# untitled.net
KiCad netlist of a schematic drawn in EAGLE
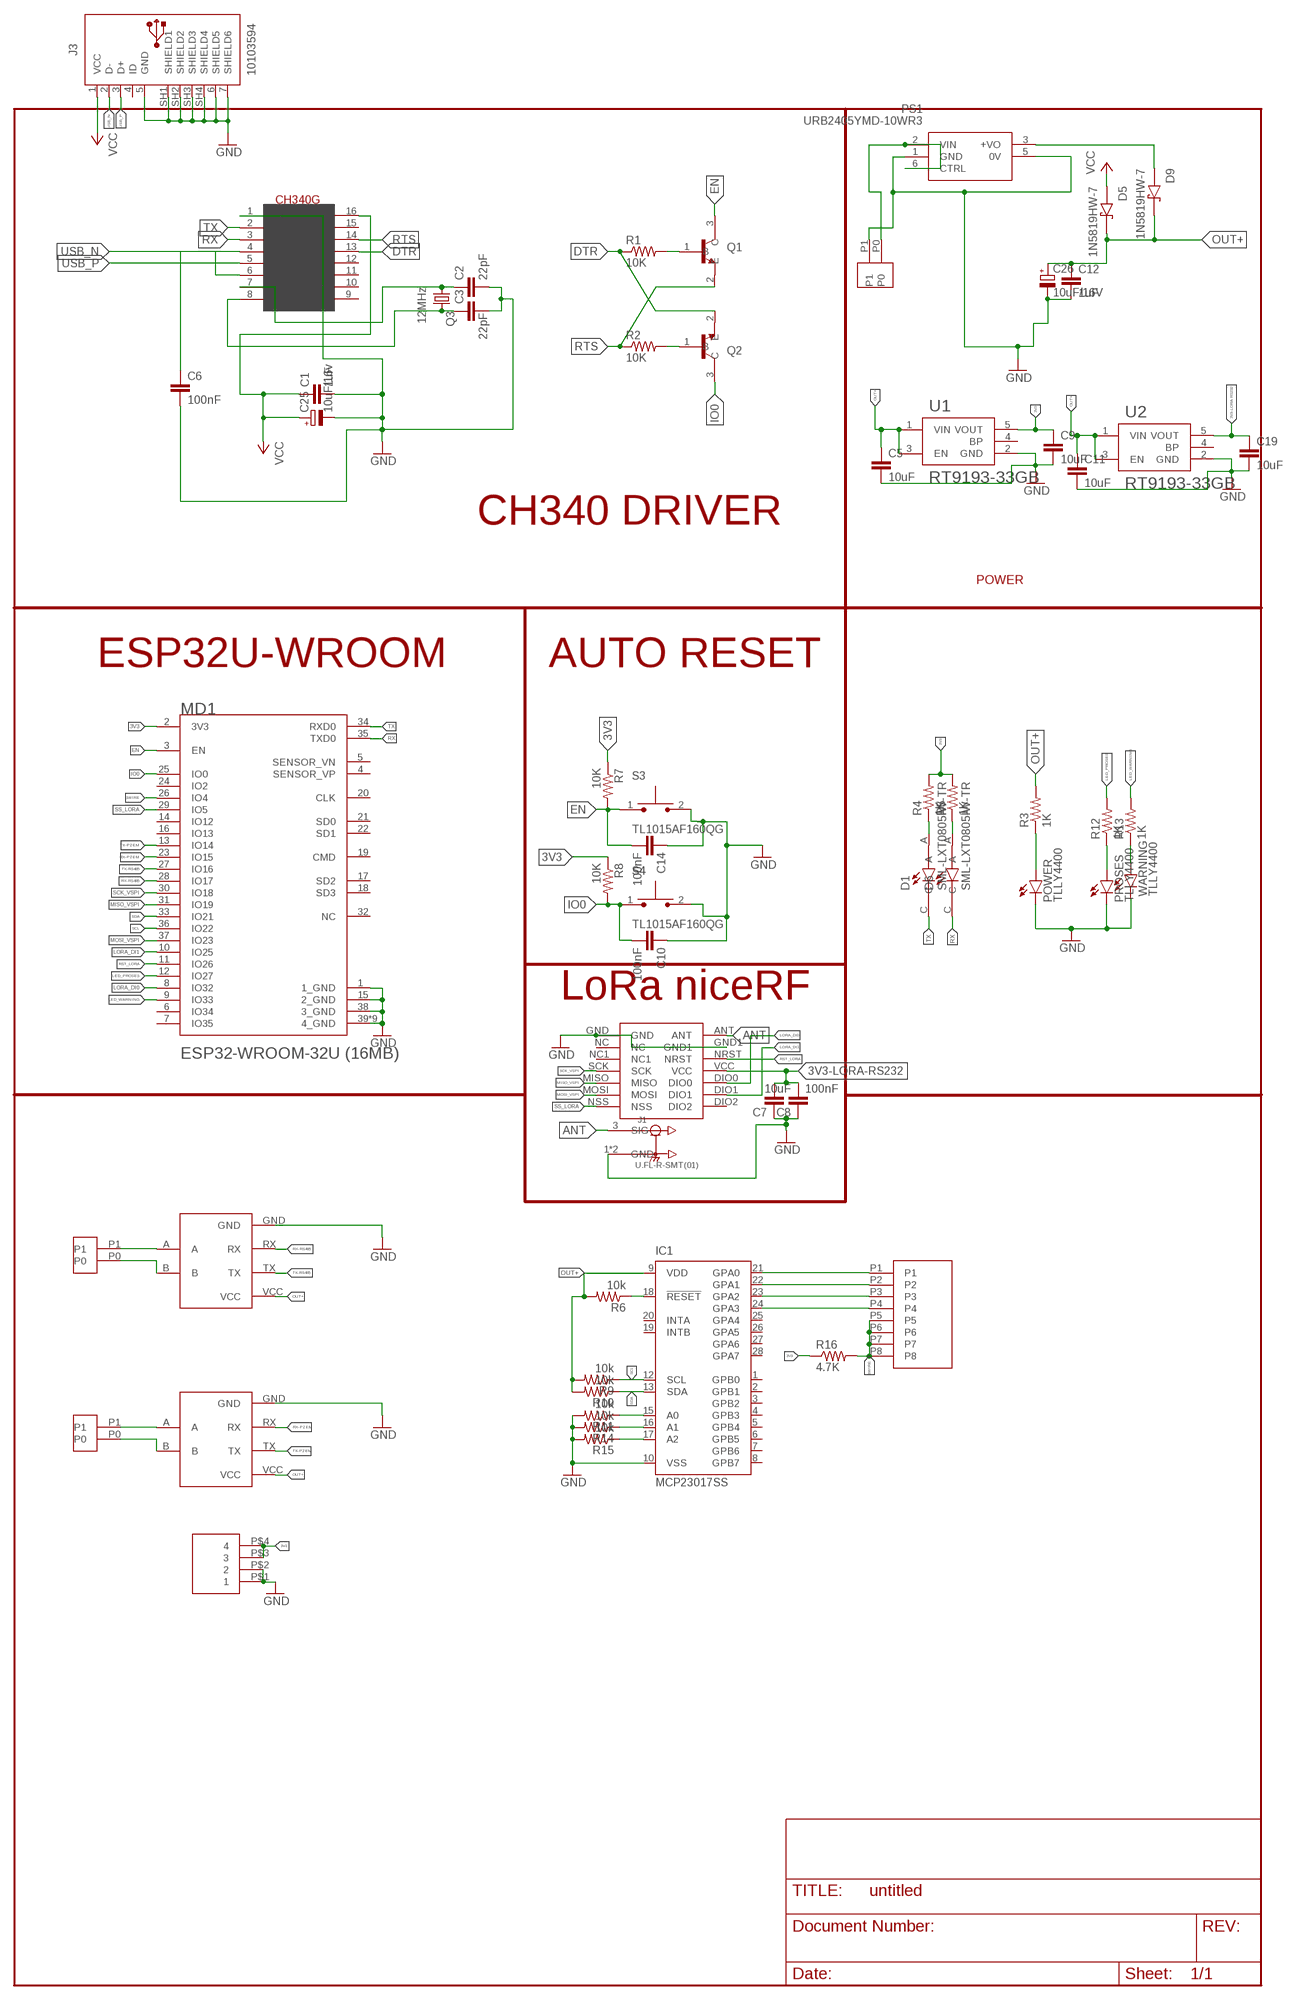
[diagram p0: schematic, sheet 1]

(export (version "E")
  (design (tool "Eeschema 10.0.6"))
  (components
    (comp (ref "C1")
      (value "1uF")
      (footprint "eagle-import:C0805K")
      (libsource (lib "eagle-import") (part "C-EUC0805K"))
    )
    (comp (ref "C2")
      (value "22pF")
      (footprint "eagle-import:C0805K")
      (libsource (lib "eagle-import") (part "C-EUC0805K"))
    )
    (comp (ref "C3")
      (value "22pF")
      (footprint "eagle-import:C0805K")
      (libsource (lib "eagle-import") (part "C-EUC0805K"))
    )
    (comp (ref "C5")
      (value "10uF")
      (footprint "eagle-import:C0805K")
      (libsource (lib "eagle-import") (part "C-EUC0805K"))
    )
    (comp (ref "C6")
      (value "100nF")
      (footprint "eagle-import:C0805K")
      (libsource (lib "eagle-import") (part "C-EUC0805K"))
    )
    (comp (ref "C7")
      (value "10uF")
      (footprint "eagle-import:C0805K")
      (libsource (lib "eagle-import") (part "C-EUC0805K"))
    )
    (comp (ref "C8")
      (value "100nF")
      (footprint "eagle-import:C0805K")
      (libsource (lib "eagle-import") (part "C-EUC0805K"))
    )
    (comp (ref "C9")
      (value "10uF")
      (footprint "eagle-import:C0805K")
      (libsource (lib "eagle-import") (part "C-EUC0805K"))
    )
    (comp (ref "C10")
      (value "100nF")
      (footprint "eagle-import:C0805K")
      (libsource (lib "eagle-import") (part "C-EUC0805K"))
    )
    (comp (ref "C11")
      (value "10uF")
      (footprint "eagle-import:C0805K")
      (libsource (lib "eagle-import") (part "C-EUC0805K"))
    )
    (comp (ref "C12")
      (value "1uF")
      (footprint "eagle-import:C0805K")
      (libsource (lib "eagle-import") (part "C-EUC0805K"))
    )
    (comp (ref "C14")
      (value "100nF")
      (footprint "eagle-import:C0805K")
      (libsource (lib "eagle-import") (part "C-EUC0805K"))
    )
    (comp (ref "C19")
      (value "10uF")
      (footprint "eagle-import:C0805K")
      (libsource (lib "eagle-import") (part "C-EUC0805K"))
    )
    (comp (ref "C25")
      (value "10uF/16v")
      (footprint "eagle-import:153CLV-0505")
      (libsource (lib "eagle-import") (part "CPOL-EU153CLV-0505"))
    )
    (comp (ref "C26")
      (value "10uF/16V")
      (footprint "eagle-import:153CLV-0505")
      (libsource (lib "eagle-import") (part "CPOL-EU153CLV-0505"))
    )
    (comp (ref "CONN2P-3.5PI1")
      (value "CONN2P-3.5PI")
      (footprint "eagle-import:CONN2P-3.5PI")
      (libsource (lib "eagle-import") (part "CONN2P-3.5PI"))
    )
    (comp (ref "CONN2P-3.5PI2")
      (value "CONN2P-3.5PI")
      (footprint "eagle-import:CONN2P-3.5PI")
      (libsource (lib "eagle-import") (part "CONN2P-3.5PI"))
    )
    (comp (ref "CONN2P-3.5PI3")
      (value "CONN2P-3.5PI")
      (footprint "eagle-import:CONN2P-3.5PI")
      (libsource (lib "eagle-import") (part "CONN2P-3.5PI"))
    )
    (comp (ref "CONN3.1")
      (value "CONN3.5")
      (footprint "eagle-import:CONN3.5")
      (libsource (lib "eagle-import") (part "CONN3.5"))
    )
    (comp (ref "D1")
      (value "SML-LXT0805IW-TR")
      (footprint "eagle-import:LEDC2012X120N")
      (fields (field (name "MF") "Lumex Opto/Components"))
      (libsource (lib "eagle-import") (part "SML-LXT0805IW-TR"))
    )
    (comp (ref "D5")
      (value "1N5819HW-7")
      (footprint "eagle-import:SOD3715X145N")
      (fields (field (name "MF") "Diodes Inc."))
      (libsource (lib "eagle-import") (part "1N5819HW-7"))
    )
    (comp (ref "D6")
      (value "SML-LXT0805IW-TR")
      (footprint "eagle-import:LEDC2012X120N")
      (fields (field (name "MF") "Lumex Opto/Components"))
      (libsource (lib "eagle-import") (part "SML-LXT0805IW-TR"))
    )
    (comp (ref "D9")
      (value "1N5819HW-7")
      (footprint "eagle-import:SOD3715X145N")
      (fields (field (name "MF") "Diodes Inc."))
      (libsource (lib "eagle-import") (part "1N5819HW-7"))
    )
    (comp (ref "HEADER-3.81-1")
      (value "HEADER-3.81-4")
      (footprint "eagle-import:HEADER-3.81-4")
      (libsource (lib "eagle-import") (part "HEADER-3.81-4"))
    )
    (comp (ref "IC1")
      (value "MCP23017SS")
      (footprint "eagle-import:SSOP28")
      (fields (field (name "MF") "MICROCHIP") (field (name "MPN") "MCP23017-E/SS"))
      (libsource (lib "eagle-import") (part "MCP23017SS"))
    )
    (comp (ref "J1")
      (value "U.FL-R-SMT(01)")
      (footprint "eagle-import:HRS_U.FL-R-SMT(01)")
      (fields (field (name "MF") "Hirose"))
      (libsource (lib "eagle-import") (part "U.FL-R-SMT(01)"))
    )
    (comp (ref "J3")
      (value "10103594")
      (footprint "eagle-import:10103594")
      (fields (field (name "MANUFACTURER") "Amphenol ICC (FCI)") (field (name "MPN") "10103594-0001LF"))
      (libsource (lib "eagle-import") (part "10103594"))
    )
    (comp (ref "LORA-NICERF-V1")
      (value "LORA-NICERF-V2")
      (footprint "eagle-import:LORA-NICERF-V2")
      (libsource (lib "eagle-import") (part "LORA-NICERF-V2"))
    )
    (comp (ref "MD1")
      (value "ESPRESSIF_SYSTEMS_ESP32-WROOM-32U_16MBESPRESSIF_SYSTEMS_ESP32-WROOM-32U_16MB_0_0")
      (footprint "eagle-import:ESPRESSIF_SYSTEMS_ESP32-WROOM-32U_16MB_0")
      (fields
        (field (name "DIGIKEY_PART_NUMBER") "1904-1028-1-ND")
        (field (name "MF") "Espressif Systems")
        (field (name "MOUSER_PART_NUMBER") "356-ES32WROOM32U16MB")
      )
      (libsource (lib "eagle-import") (part "ESPRESSIF_SYSTEMS_ESP32-WROOM-32U_16MBESPRESSIF_SYSTEMS_ESP32-WROOM-32U_16MB_0_0"))
    )
    (comp (ref "POWER")
      (value "TLLY4400")
      (footprint "eagle-import:LED3MM")
      (fields (field (name "MF") "VISHAY SEMICONDUCTOR"))
      (libsource (lib "eagle-import") (part "TLLY4400"))
    )
    (comp (ref "PROSES")
      (value "TLLY4400")
      (footprint "eagle-import:LED3MM")
      (fields (field (name "MF") "VISHAY SEMICONDUCTOR"))
      (libsource (lib "eagle-import") (part "TLLY4400"))
    )
    (comp (ref "PS1")
      (value "URB2405YMD-10WR3")
      (footprint "eagle-import:URB2405YMD10WR3")
      (libsource (lib "eagle-import") (part "URB2405YMD-10WR3"))
    )
    (comp (ref "Q1")
      (value "MMBT3904")
      (footprint "eagle-import:SOT95P240X120-3N")
      (fields (field (name "MF") "STMicroelectronics"))
      (libsource (lib "eagle-import") (part "MMBT3904"))
    )
    (comp (ref "Q2")
      (value "MMBT3904")
      (footprint "eagle-import:SOT95P240X120-3N")
      (fields (field (name "MF") "STMicroelectronics"))
      (libsource (lib "eagle-import") (part "MMBT3904"))
    )
    (comp (ref "Q3")
      (value "12MHz")
      (footprint "eagle-import:SM49")
      (libsource (lib "eagle-import") (part "CRYSTALSM49"))
    )
    (comp (ref "R1")
      (value "10K")
      (footprint "eagle-import:M0805")
      (libsource (lib "eagle-import") (part "R-US_M0805"))
    )
    (comp (ref "R2")
      (value "10K")
      (footprint "eagle-import:M0805")
      (libsource (lib "eagle-import") (part "R-US_M0805"))
    )
    (comp (ref "R3")
      (value "1K")
      (footprint "eagle-import:M0805")
      (libsource (lib "eagle-import") (part "R-US_M0805"))
    )
    (comp (ref "R4")
      (value "1K")
      (footprint "eagle-import:M0805")
      (libsource (lib "eagle-import") (part "R-US_M0805"))
    )
    (comp (ref "R5")
      (value "1K")
      (footprint "eagle-import:M0805")
      (libsource (lib "eagle-import") (part "R-US_M0805"))
    )
    (comp (ref "R6")
      (value "10k")
      (footprint "eagle-import:M0805")
      (libsource (lib "eagle-import") (part "R-US_M0805"))
    )
    (comp (ref "R7")
      (value "10K")
      (footprint "eagle-import:M0805")
      (libsource (lib "eagle-import") (part "R-US_M0805"))
    )
    (comp (ref "R8")
      (value "10K")
      (footprint "eagle-import:M0805")
      (libsource (lib "eagle-import") (part "R-US_M0805"))
    )
    (comp (ref "R9")
      (value "10k")
      (footprint "eagle-import:M0805")
      (libsource (lib "eagle-import") (part "R-US_M0805"))
    )
    (comp (ref "R10")
      (value "10k")
      (footprint "eagle-import:M0805")
      (libsource (lib "eagle-import") (part "R-US_M0805"))
    )
    (comp (ref "R11")
      (value "10k")
      (footprint "eagle-import:M0805")
      (libsource (lib "eagle-import") (part "R-US_M0805"))
    )
    (comp (ref "R12")
      (value "1K")
      (footprint "eagle-import:M0805")
      (libsource (lib "eagle-import") (part "R-US_M0805"))
    )
    (comp (ref "R13")
      (value "1K")
      (footprint "eagle-import:M0805")
      (libsource (lib "eagle-import") (part "R-US_M0805"))
    )
    (comp (ref "R14")
      (value "10k")
      (footprint "eagle-import:M0805")
      (libsource (lib "eagle-import") (part "R-US_M0805"))
    )
    (comp (ref "R15")
      (value "10k")
      (footprint "eagle-import:M0805")
      (libsource (lib "eagle-import") (part "R-US_M0805"))
    )
    (comp (ref "R16")
      (value "4.7K")
      (footprint "eagle-import:M0805")
      (libsource (lib "eagle-import") (part "R-US_M0805"))
    )
    (comp (ref "S3")
      (value "TL1015AF160QG")
      (footprint "eagle-import:SW_TL1015AF160QG")
      (fields (field (name "MF") "E-Switch"))
      (libsource (lib "eagle-import") (part "TL1015AF160QG"))
    )
    (comp (ref "S4")
      (value "TL1015AF160QG")
      (footprint "eagle-import:SW_TL1015AF160QG")
      (fields (field (name "MF") "E-Switch"))
      (libsource (lib "eagle-import") (part "TL1015AF160QG"))
    )
    (comp (ref "TTL-RS1")
      (value "TTL-RS485")
      (footprint "eagle-import:TTL-RS485")
      (libsource (lib "eagle-import") (part "TTL-RS485"))
    )
    (comp (ref "TTL-RS2")
      (value "TTL-RS485")
      (footprint "eagle-import:TTL-RS485")
      (libsource (lib "eagle-import") (part "TTL-RS485"))
    )
    (comp (ref "U$2")
      (value "CH340G")
      (footprint "eagle-import:SOIC16")
      (libsource (lib "eagle-import") (part "CH340G"))
    )
    (comp (ref "U1")
      (value "RT9193-33GB")
      (footprint "eagle-import:SOT94P279X129-5N")
      (fields (field (name "MF") "Richtek USA Inc."))
      (libsource (lib "eagle-import") (part "RT9193-33GB"))
    )
    (comp (ref "U2")
      (value "RT9193-33GB")
      (footprint "eagle-import:SOT94P279X129-5N")
      (fields (field (name "MF") "Richtek USA Inc."))
      (libsource (lib "eagle-import") (part "RT9193-33GB"))
    )
    (comp (ref "WARNING")
      (value "TLLY4400")
      (footprint "eagle-import:LED3MM")
      (fields (field (name "MF") "VISHAY SEMICONDUCTOR"))
      (libsource (lib "eagle-import") (part "TLLY4400"))
    )
  )
  (nets
    (net (code "1") (name "1WIRE") (class "Default")
      (node (ref "CONN3.1") (pin "P5") (pinfunction "P5_P5") (pintype "bidirectional"))
      (node (ref "CONN3.1") (pin "P6") (pinfunction "P6_P6") (pintype "bidirectional"))
      (node (ref "CONN3.1") (pin "P7") (pinfunction "P7_P7") (pintype "bidirectional"))
      (node (ref "CONN3.1") (pin "P8") (pinfunction "P8_P8") (pintype "bidirectional"))
      (node (ref "MD1") (pin "26") (pinfunction "IO4_26") (pintype "bidirectional"))
      (node (ref "R16") (pin "2") (pinfunction "2_2") (pintype "passive"))
    )
    (net (code "2") (name "3V3") (class "Default")
      (node (ref "C9") (pin "1") (pinfunction "1_1") (pintype "passive"))
      (node (ref "HEADER-3.81-1") (pin "P$3") (pinfunction "3_P$3") (pintype "bidirectional"))
      (node (ref "HEADER-3.81-1") (pin "P$4") (pinfunction "4_P$4") (pintype "bidirectional"))
      (node (ref "MD1") (pin "2") (pinfunction "3V3_2") (pintype "power_in"))
      (node (ref "R16") (pin "1") (pinfunction "1_1") (pintype "passive"))
      (node (ref "R4") (pin "2") (pinfunction "2_2") (pintype "passive"))
      (node (ref "R5") (pin "2") (pinfunction "2_2") (pintype "passive"))
      (node (ref "R7") (pin "1") (pinfunction "1_1") (pintype "passive"))
      (node (ref "R8") (pin "1") (pinfunction "1_1") (pintype "passive"))
      (node (ref "U1") (pin "5") (pinfunction "VOUT_5") (pintype "output"))
    )
    (net (code "3") (name "3V3-LORA-RS232") (class "Default")
      (node (ref "C19") (pin "1") (pinfunction "1_1") (pintype "passive"))
      (node (ref "C7") (pin "2") (pinfunction "2_2") (pintype "passive"))
      (node (ref "C8") (pin "2") (pinfunction "2_2") (pintype "passive"))
      (node (ref "LORA-NICERF-V1") (pin "VCC") (pinfunction "VCC_VCC") (pintype "bidirectional"))
      (node (ref "U2") (pin "5") (pinfunction "VOUT_5") (pintype "output"))
    )
    (net (code "4") (name "ANT") (class "Default")
      (node (ref "J1") (pin "3") (pinfunction "SIG_3") (pintype "passive"))
      (node (ref "LORA-NICERF-V1") (pin "ANT") (pinfunction "ANT_ANT") (pintype "bidirectional"))
    )
    (net (code "5") (name "DTR") (class "Default")
      (node (ref "Q2") (pin "2") (pinfunction "E_2") (pintype "passive"))
      (node (ref "R1") (pin "1") (pinfunction "1_1") (pintype "passive"))
      (node (ref "U$2") (pin "13") (pinfunction "DTR_13") (pintype "bidirectional"))
    )
    (net (code "6") (name "EN") (class "Default")
      (node (ref "C14") (pin "2") (pinfunction "2_2") (pintype "passive"))
      (node (ref "MD1") (pin "3") (pinfunction "EN_3") (pintype "input"))
      (node (ref "Q1") (pin "3") (pinfunction "C_3") (pintype "passive"))
      (node (ref "R7") (pin "2") (pinfunction "2_2") (pintype "passive"))
      (node (ref "S3") (pin "1") (pinfunction "1_1") (pintype "passive"))
    )
    (net (code "7") (name "GND") (class "Default")
      (node (ref "C1") (pin "2") (pinfunction "2_2") (pintype "passive"))
      (node (ref "C10") (pin "1") (pinfunction "1_1") (pintype "passive"))
      (node (ref "C11") (pin "2") (pinfunction "2_2") (pintype "passive"))
      (node (ref "C12") (pin "2") (pinfunction "2_2") (pintype "passive"))
      (node (ref "C14") (pin "1") (pinfunction "1_1") (pintype "passive"))
      (node (ref "C19") (pin "2") (pinfunction "2_2") (pintype "passive"))
      (node (ref "C2") (pin "2") (pinfunction "2_2") (pintype "passive"))
      (node (ref "C25") (pin "-") (pinfunction "-_-") (pintype "passive"))
      (node (ref "C26") (pin "-") (pinfunction "-_-") (pintype "passive"))
      (node (ref "C3") (pin "2") (pinfunction "2_2") (pintype "passive"))
      (node (ref "C5") (pin "2") (pinfunction "2_2") (pintype "passive"))
      (node (ref "C6") (pin "2") (pinfunction "2_2") (pintype "passive"))
      (node (ref "C7") (pin "1") (pinfunction "1_1") (pintype "passive"))
      (node (ref "C8") (pin "1") (pinfunction "1_1") (pintype "passive"))
      (node (ref "C9") (pin "2") (pinfunction "2_2") (pintype "passive"))
      (node (ref "CONN2P-3.5PI1") (pin "P1") (pinfunction "P1_P1") (pintype "bidirectional"))
      (node (ref "HEADER-3.81-1") (pin "P$1") (pinfunction "1_P$1") (pintype "bidirectional"))
      (node (ref "HEADER-3.81-1") (pin "P$2") (pinfunction "2_P$2") (pintype "bidirectional"))
      (node (ref "IC1") (pin "10") (pinfunction "VSS_10") (pintype "power_in"))
      (node (ref "J1") (pin "1") (pinfunction "GND_1") (pintype "passive"))
      (node (ref "J1") (pin "2") (pinfunction "GND_2") (pintype "passive"))
      (node (ref "J3") (pin "5") (pinfunction "GND_5") (pintype "power_in"))
      (node (ref "J3") (pin "6") (pinfunction "SHIELD5_6") (pintype "power_in"))
      (node (ref "J3") (pin "7") (pinfunction "SHIELD6_7") (pintype "power_in"))
      (node (ref "J3") (pin "SH1") (pinfunction "SHIELD1_SH1") (pintype "power_in"))
      (node (ref "J3") (pin "SH2") (pinfunction "SHIELD2_SH2") (pintype "power_in"))
      (node (ref "J3") (pin "SH3") (pinfunction "SHIELD3_SH3") (pintype "power_in"))
      (node (ref "J3") (pin "SH4") (pinfunction "SHIELD4_SH4") (pintype "power_in"))
      (node (ref "LORA-NICERF-V1") (pin "GND") (pinfunction "GND_GND") (pintype "bidirectional"))
      (node (ref "LORA-NICERF-V1") (pin "GND1") (pinfunction "GND1_GND1") (pintype "bidirectional"))
      (node (ref "MD1") (pin "1") (pinfunction "1_GND_1") (pintype "power_in"))
      (node (ref "MD1") (pin "15") (pinfunction "2_GND_15") (pintype "power_in"))
      (node (ref "MD1") (pin "38") (pinfunction "3_GND_38") (pintype "power_in"))
      (node (ref "MD1") (pin "39") (pinfunction "4_GND_39") (pintype "power_in"))
      (node (ref "MD1") (pin "39-2") (pinfunction "4_GND_39-2") (pintype "power_in"))
      (node (ref "MD1") (pin "39-3") (pinfunction "4_GND_39-3") (pintype "power_in"))
      (node (ref "MD1") (pin "39-4") (pinfunction "4_GND_39-4") (pintype "power_in"))
      (node (ref "MD1") (pin "39-5") (pinfunction "4_GND_39-5") (pintype "power_in"))
      (node (ref "MD1") (pin "39-6") (pinfunction "4_GND_39-6") (pintype "power_in"))
      (node (ref "MD1") (pin "39-7") (pinfunction "4_GND_39-7") (pintype "power_in"))
      (node (ref "MD1") (pin "39-8") (pinfunction "4_GND_39-8") (pintype "power_in"))
      (node (ref "MD1") (pin "39-9") (pinfunction "4_GND_39-9") (pintype "power_in"))
      (node (ref "POWER") (pin "K") (pinfunction "C_K") (pintype "passive"))
      (node (ref "PROSES") (pin "K") (pinfunction "C_K") (pintype "passive"))
      (node (ref "PS1") (pin "1") (pinfunction "GND_1") (pintype "bidirectional"))
      (node (ref "PS1") (pin "5") (pinfunction "0V_5") (pintype "bidirectional"))
      (node (ref "R11") (pin "2") (pinfunction "2_2") (pintype "passive"))
      (node (ref "R14") (pin "2") (pinfunction "2_2") (pintype "passive"))
      (node (ref "R15") (pin "2") (pinfunction "2_2") (pintype "passive"))
      (node (ref "S3") (pin "2") (pinfunction "2_2") (pintype "passive"))
      (node (ref "S4") (pin "2") (pinfunction "2_2") (pintype "passive"))
      (node (ref "TTL-RS1") (pin "GND") (pinfunction "GND_GND") (pintype "bidirectional"))
      (node (ref "TTL-RS2") (pin "GND") (pinfunction "GND_GND") (pintype "bidirectional"))
      (node (ref "U$2") (pin "1") (pinfunction "GND_1") (pintype "bidirectional"))
      (node (ref "U1") (pin "2") (pinfunction "GND_2") (pintype "power_in"))
      (node (ref "U2") (pin "2") (pinfunction "GND_2") (pintype "power_in"))
      (node (ref "WARNING") (pin "K") (pinfunction "C_K") (pintype "passive"))
    )
    (net (code "8") (name "IO0") (class "Default")
      (node (ref "C10") (pin "2") (pinfunction "2_2") (pintype "passive"))
      (node (ref "MD1") (pin "25") (pinfunction "IO0_25") (pintype "bidirectional"))
      (node (ref "Q2") (pin "3") (pinfunction "C_3") (pintype "passive"))
      (node (ref "R8") (pin "2") (pinfunction "2_2") (pintype "passive"))
      (node (ref "S4") (pin "1") (pinfunction "1_1") (pintype "passive"))
    )
    (net (code "9") (name "LED_PROSES") (class "Default")
      (node (ref "MD1") (pin "12") (pinfunction "IO27_12") (pintype "bidirectional"))
      (node (ref "R12") (pin "2") (pinfunction "2_2") (pintype "passive"))
    )
    (net (code "10") (name "LED_WARNING") (class "Default")
      (node (ref "MD1") (pin "9") (pinfunction "IO33_9") (pintype "bidirectional"))
      (node (ref "R13") (pin "2") (pinfunction "2_2") (pintype "passive"))
    )
    (net (code "11") (name "LORA_DI0") (class "Default")
      (node (ref "LORA-NICERF-V1") (pin "DIO0") (pinfunction "DIO0_DIO0") (pintype "bidirectional"))
      (node (ref "MD1") (pin "8") (pinfunction "IO32_8") (pintype "bidirectional"))
    )
    (net (code "12") (name "LORA_DI1") (class "Default")
      (node (ref "LORA-NICERF-V1") (pin "DIO1") (pinfunction "DIO1_DIO1") (pintype "bidirectional"))
      (node (ref "MD1") (pin "10") (pinfunction "IO25_10") (pintype "bidirectional"))
    )
    (net (code "13") (name "MISO_VSPI") (class "Default")
      (node (ref "LORA-NICERF-V1") (pin "MISO") (pinfunction "MISO_MISO") (pintype "bidirectional"))
      (node (ref "MD1") (pin "31") (pinfunction "IO19_31") (pintype "bidirectional"))
    )
    (net (code "14") (name "MOSI_VSPI") (class "Default")
      (node (ref "LORA-NICERF-V1") (pin "MOSI") (pinfunction "MOSI_MOSI") (pintype "bidirectional"))
      (node (ref "MD1") (pin "37") (pinfunction "IO23_37") (pintype "bidirectional"))
    )
    (net (code "15") (name "Net-(CONN2P-3.5PI2-PadP0)") (class "Default")
      (node (ref "CONN2P-3.5PI2") (pin "P0") (pinfunction "P0_P0") (pintype "bidirectional"))
      (node (ref "TTL-RS1") (pin "B") (pinfunction "B_B") (pintype "bidirectional"))
    )
    (net (code "16") (name "Net-(CONN2P-3.5PI2-PadP1)") (class "Default")
      (node (ref "CONN2P-3.5PI2") (pin "P1") (pinfunction "P1_P1") (pintype "bidirectional"))
      (node (ref "TTL-RS1") (pin "A") (pinfunction "A_A") (pintype "bidirectional"))
    )
    (net (code "17") (name "Net-(CONN2P-3.5PI3-PadP0)") (class "Default")
      (node (ref "CONN2P-3.5PI3") (pin "P0") (pinfunction "P0_P0") (pintype "bidirectional"))
      (node (ref "TTL-RS2") (pin "B") (pinfunction "B_B") (pintype "bidirectional"))
    )
    (net (code "18") (name "Net-(CONN2P-3.5PI3-PadP1)") (class "Default")
      (node (ref "CONN2P-3.5PI3") (pin "P1") (pinfunction "P1_P1") (pintype "bidirectional"))
      (node (ref "TTL-RS2") (pin "A") (pinfunction "A_A") (pintype "bidirectional"))
    )
    (net (code "19") (name "Net-(D1-PadA)") (class "Default")
      (node (ref "D1") (pin "A") (pinfunction "A_A") (pintype "passive"))
      (node (ref "R4") (pin "1") (pinfunction "1_1") (pintype "passive"))
    )
    (net (code "20") (name "Net-(D6-PadA)") (class "Default")
      (node (ref "D6") (pin "A") (pinfunction "A_A") (pintype "passive"))
      (node (ref "R5") (pin "1") (pinfunction "1_1") (pintype "passive"))
    )
    (net (code "21") (name "Net-(IC1-A0)") (class "Default")
      (node (ref "IC1") (pin "15") (pinfunction "A0_15") (pintype "input"))
      (node (ref "R11") (pin "1") (pinfunction "1_1") (pintype "passive"))
    )
    (net (code "22") (name "Net-(IC1-A1)") (class "Default")
      (node (ref "IC1") (pin "16") (pinfunction "A1_16") (pintype "input"))
      (node (ref "R14") (pin "1") (pinfunction "1_1") (pintype "passive"))
    )
    (net (code "23") (name "Net-(IC1-A2)") (class "Default")
      (node (ref "IC1") (pin "17") (pinfunction "A2_17") (pintype "input"))
      (node (ref "R15") (pin "1") (pinfunction "1_1") (pintype "passive"))
    )
    (net (code "24") (name "Net-(IC1-GPA0)") (class "Default")
      (node (ref "CONN3.1") (pin "P1") (pinfunction "P1_P1") (pintype "bidirectional"))
      (node (ref "IC1") (pin "21") (pinfunction "GPA0_21") (pintype "bidirectional"))
    )
    (net (code "25") (name "Net-(IC1-GPA1)") (class "Default")
      (node (ref "CONN3.1") (pin "P2") (pinfunction "P2_P2") (pintype "bidirectional"))
      (node (ref "IC1") (pin "22") (pinfunction "GPA1_22") (pintype "bidirectional"))
    )
    (net (code "26") (name "Net-(IC1-GPA2)") (class "Default")
      (node (ref "CONN3.1") (pin "P3") (pinfunction "P3_P3") (pintype "bidirectional"))
      (node (ref "IC1") (pin "23") (pinfunction "GPA2_23") (pintype "bidirectional"))
    )
    (net (code "27") (name "Net-(IC1-GPA3)") (class "Default")
      (node (ref "CONN3.1") (pin "P4") (pinfunction "P4_P4") (pintype "bidirectional"))
      (node (ref "IC1") (pin "24") (pinfunction "GPA3_24") (pintype "bidirectional"))
    )
    (net (code "28") (name "Net-(IC1-~{RESET})") (class "Default")
      (node (ref "IC1") (pin "18") (pinfunction "~{RESET}_18") (pintype "input"))
      (node (ref "R6") (pin "1") (pinfunction "1_1") (pintype "passive"))
    )
    (net (code "29") (name "Net-(POWER-PadA)") (class "Default")
      (node (ref "POWER") (pin "A") (pinfunction "A_A") (pintype "passive"))
      (node (ref "R3") (pin "1") (pinfunction "1_1") (pintype "passive"))
    )
    (net (code "30") (name "Net-(PROSES-PadA)") (class "Default")
      (node (ref "PROSES") (pin "A") (pinfunction "A_A") (pintype "passive"))
      (node (ref "R12") (pin "1") (pinfunction "1_1") (pintype "passive"))
    )
    (net (code "31") (name "Net-(PS1-+VO)") (class "Default")
      (node (ref "D9") (pin "A") (pinfunction "A_A") (pintype "passive"))
      (node (ref "PS1") (pin "3") (pinfunction "+VO_3") (pintype "bidirectional"))
    )
    (net (code "32") (name "Net-(PS1-CTRL)") (class "Default")
      (node (ref "CONN2P-3.5PI1") (pin "P0") (pinfunction "P0_P0") (pintype "bidirectional"))
      (node (ref "PS1") (pin "2") (pinfunction "VIN_2") (pintype "bidirectional"))
      (node (ref "PS1") (pin "6") (pinfunction "CTRL_6") (pintype "bidirectional"))
    )
    (net (code "33") (name "Net-(Q1-B)") (class "Default")
      (node (ref "Q1") (pin "1") (pinfunction "B_1") (pintype "passive"))
      (node (ref "R1") (pin "2") (pinfunction "2_2") (pintype "passive"))
    )
    (net (code "34") (name "Net-(Q2-B)") (class "Default")
      (node (ref "Q2") (pin "1") (pinfunction "B_1") (pintype "passive"))
      (node (ref "R2") (pin "2") (pinfunction "2_2") (pintype "passive"))
    )
    (net (code "35") (name "Net-(R13-Pad1)") (class "Default")
      (node (ref "R13") (pin "1") (pinfunction "1_1") (pintype "passive"))
      (node (ref "WARNING") (pin "A") (pinfunction "A_A") (pintype "passive"))
    )
    (net (code "36") (name "Net-(U$2-V3)") (class "Default")
      (node (ref "C6") (pin "1") (pinfunction "1_1") (pintype "passive"))
      (node (ref "U$2") (pin "4") (pinfunction "V3_4") (pintype "bidirectional"))
    )
    (net (code "37") (name "Net-(U$2-XI)") (class "Default")
      (node (ref "C2") (pin "1") (pinfunction "1_1") (pintype "passive"))
      (node (ref "Q3") (pin "1") (pinfunction "1_1") (pintype "passive"))
      (node (ref "U$2") (pin "7") (pinfunction "XI_7") (pintype "bidirectional"))
    )
    (net (code "38") (name "Net-(U$2-XO)") (class "Default")
      (node (ref "C3") (pin "1") (pinfunction "1_1") (pintype "passive"))
      (node (ref "Q3") (pin "2") (pinfunction "2_2") (pintype "passive"))
      (node (ref "U$2") (pin "8") (pinfunction "XO_8") (pintype "bidirectional"))
    )
    (net (code "39") (name "OUT+") (class "Default")
      (node (ref "C11") (pin "1") (pinfunction "1_1") (pintype "passive"))
      (node (ref "C12") (pin "1") (pinfunction "1_1") (pintype "passive"))
      (node (ref "C26") (pin "+") (pinfunction "+_+") (pintype "passive"))
      (node (ref "C5") (pin "1") (pinfunction "1_1") (pintype "passive"))
      (node (ref "D5") (pin "C") (pinfunction "K_C") (pintype "passive"))
      (node (ref "D9") (pin "C") (pinfunction "K_C") (pintype "passive"))
      (node (ref "IC1") (pin "9") (pinfunction "VDD_9") (pintype "power_in"))
      (node (ref "R10") (pin "2") (pinfunction "2_2") (pintype "passive"))
      (node (ref "R3") (pin "2") (pinfunction "2_2") (pintype "passive"))
      (node (ref "R6") (pin "2") (pinfunction "2_2") (pintype "passive"))
      (node (ref "R9") (pin "2") (pinfunction "2_2") (pintype "passive"))
      (node (ref "TTL-RS1") (pin "VCC") (pinfunction "VCC_VCC") (pintype "bidirectional"))
      (node (ref "TTL-RS2") (pin "VCC") (pinfunction "VCC_VCC") (pintype "bidirectional"))
      (node (ref "U1") (pin "1") (pinfunction "VIN_1") (pintype "input"))
      (node (ref "U1") (pin "3") (pinfunction "EN_3") (pintype "input"))
      (node (ref "U2") (pin "1") (pinfunction "VIN_1") (pintype "input"))
      (node (ref "U2") (pin "3") (pinfunction "EN_3") (pintype "input"))
    )
    (net (code "40") (name "RST_LORA") (class "Default")
      (node (ref "LORA-NICERF-V1") (pin "NRST") (pinfunction "NRST_NRST") (pintype "bidirectional"))
      (node (ref "MD1") (pin "11") (pinfunction "IO26_11") (pintype "bidirectional"))
    )
    (net (code "41") (name "RTS") (class "Default")
      (node (ref "Q1") (pin "2") (pinfunction "E_2") (pintype "passive"))
      (node (ref "R2") (pin "1") (pinfunction "1_1") (pintype "passive"))
      (node (ref "U$2") (pin "14") (pinfunction "RTS_14") (pintype "bidirectional"))
    )
    (net (code "42") (name "RX") (class "Default")
      (node (ref "D6") (pin "C") (pinfunction "C_C") (pintype "passive"))
      (node (ref "MD1") (pin "35") (pinfunction "TXD0_35") (pintype "bidirectional"))
      (node (ref "U$2") (pin "3") (pinfunction "RX_3") (pintype "bidirectional"))
    )
    (net (code "43") (name "RX-PZEM") (class "Default")
      (node (ref "MD1") (pin "23") (pinfunction "IO15_23") (pintype "bidirectional"))
      (node (ref "TTL-RS2") (pin "RX") (pinfunction "RX_RX") (pintype "bidirectional"))
    )
    (net (code "44") (name "RX-RS485") (class "Default")
      (node (ref "MD1") (pin "28") (pinfunction "IO17_28") (pintype "bidirectional"))
      (node (ref "TTL-RS1") (pin "RX") (pinfunction "RX_RX") (pintype "bidirectional"))
    )
    (net (code "45") (name "SCK_VSPI") (class "Default")
      (node (ref "LORA-NICERF-V1") (pin "SCK") (pinfunction "SCK_SCK") (pintype "bidirectional"))
      (node (ref "MD1") (pin "30") (pinfunction "IO18_30") (pintype "bidirectional"))
    )
    (net (code "46") (name "SCL") (class "Default")
      (node (ref "IC1") (pin "12") (pinfunction "SCL_12") (pintype "input"))
      (node (ref "MD1") (pin "36") (pinfunction "IO22_36") (pintype "bidirectional"))
      (node (ref "R9") (pin "1") (pinfunction "1_1") (pintype "passive"))
    )
    (net (code "47") (name "SDA") (class "Default")
      (node (ref "IC1") (pin "13") (pinfunction "SDA_13") (pintype "bidirectional"))
      (node (ref "MD1") (pin "33") (pinfunction "IO21_33") (pintype "bidirectional"))
      (node (ref "R10") (pin "1") (pinfunction "1_1") (pintype "passive"))
    )
    (net (code "48") (name "SS_LORA") (class "Default")
      (node (ref "LORA-NICERF-V1") (pin "NSS") (pinfunction "NSS_NSS") (pintype "bidirectional"))
      (node (ref "MD1") (pin "29") (pinfunction "IO5_29") (pintype "bidirectional"))
    )
    (net (code "49") (name "TX") (class "Default")
      (node (ref "D1") (pin "C") (pinfunction "C_C") (pintype "passive"))
      (node (ref "MD1") (pin "34") (pinfunction "RXD0_34") (pintype "bidirectional"))
      (node (ref "U$2") (pin "2") (pinfunction "TX_2") (pintype "bidirectional"))
    )
    (net (code "50") (name "TX-PZEM") (class "Default")
      (node (ref "MD1") (pin "13") (pinfunction "IO14_13") (pintype "bidirectional"))
      (node (ref "TTL-RS2") (pin "TX") (pinfunction "TX_TX") (pintype "bidirectional"))
    )
    (net (code "51") (name "TX-RS485") (class "Default")
      (node (ref "MD1") (pin "27") (pinfunction "IO16_27") (pintype "bidirectional"))
      (node (ref "TTL-RS1") (pin "TX") (pinfunction "TX_TX") (pintype "bidirectional"))
    )
    (net (code "52") (name "USB_N") (class "Default")
      (node (ref "J3") (pin "2") (pinfunction "D-_2") (pintype "bidirectional"))
      (node (ref "U$2") (pin "6") (pinfunction "D-_6") (pintype "bidirectional"))
    )
    (net (code "53") (name "USB_P") (class "Default")
      (node (ref "J3") (pin "3") (pinfunction "D+_3") (pintype "bidirectional"))
      (node (ref "U$2") (pin "5") (pinfunction "D+_5") (pintype "bidirectional"))
    )
    (net (code "54") (name "VCC") (class "Default")
      (node (ref "C1") (pin "1") (pinfunction "1_1") (pintype "passive"))
      (node (ref "C25") (pin "+") (pinfunction "+_+") (pintype "passive"))
      (node (ref "D5") (pin "A") (pinfunction "A_A") (pintype "passive"))
      (node (ref "J3") (pin "1") (pinfunction "VCC_1") (pintype "power_in"))
      (node (ref "U$2") (pin "16") (pinfunction "VCC_16") (pintype "bidirectional"))
    )
    (net (code "55") (name "unconnected-(IC1-GPA4-Pad25)") (class "Default")
      (node (ref "IC1") (pin "25") (pinfunction "GPA4_25") (pintype "bidirectional"))
    )
    (net (code "56") (name "unconnected-(IC1-GPA5-Pad26)") (class "Default")
      (node (ref "IC1") (pin "26") (pinfunction "GPA5_26") (pintype "bidirectional"))
    )
    (net (code "57") (name "unconnected-(IC1-GPA6-Pad27)") (class "Default")
      (node (ref "IC1") (pin "27") (pinfunction "GPA6_27") (pintype "bidirectional"))
    )
    (net (code "58") (name "unconnected-(IC1-GPA7-Pad28)") (class "Default")
      (node (ref "IC1") (pin "28") (pinfunction "GPA7_28") (pintype "bidirectional"))
    )
    (net (code "59") (name "unconnected-(IC1-GPB0-Pad1)") (class "Default")
      (node (ref "IC1") (pin "1") (pinfunction "GPB0_1") (pintype "bidirectional"))
    )
    (net (code "60") (name "unconnected-(IC1-GPB1-Pad2)") (class "Default")
      (node (ref "IC1") (pin "2") (pinfunction "GPB1_2") (pintype "bidirectional"))
    )
    (net (code "61") (name "unconnected-(IC1-GPB2-Pad3)") (class "Default")
      (node (ref "IC1") (pin "3") (pinfunction "GPB2_3") (pintype "bidirectional"))
    )
    (net (code "62") (name "unconnected-(IC1-GPB3-Pad4)") (class "Default")
      (node (ref "IC1") (pin "4") (pinfunction "GPB3_4") (pintype "bidirectional"))
    )
    (net (code "63") (name "unconnected-(IC1-GPB4-Pad5)") (class "Default")
      (node (ref "IC1") (pin "5") (pinfunction "GPB4_5") (pintype "bidirectional"))
    )
    (net (code "64") (name "unconnected-(IC1-GPB5-Pad6)") (class "Default")
      (node (ref "IC1") (pin "6") (pinfunction "GPB5_6") (pintype "bidirectional"))
    )
    (net (code "65") (name "unconnected-(IC1-GPB6-Pad7)") (class "Default")
      (node (ref "IC1") (pin "7") (pinfunction "GPB6_7") (pintype "bidirectional"))
    )
    (net (code "66") (name "unconnected-(IC1-GPB7-Pad8)") (class "Default")
      (node (ref "IC1") (pin "8") (pinfunction "GPB7_8") (pintype "bidirectional"))
    )
    (net (code "67") (name "unconnected-(IC1-INTA-Pad20)") (class "Default")
      (node (ref "IC1") (pin "20") (pinfunction "INTA_20") (pintype "output"))
    )
    (net (code "68") (name "unconnected-(IC1-INTB-Pad19)") (class "Default")
      (node (ref "IC1") (pin "19") (pinfunction "INTB_19") (pintype "output"))
    )
    (net (code "69") (name "unconnected-(J3-ID-Pad4)") (class "Default")
      (node (ref "J3") (pin "4") (pinfunction "ID_4") (pintype "bidirectional"))
    )
    (net (code "70") (name "unconnected-(LORA-NICERF-V1-PadDIO2)") (class "Default")
      (node (ref "LORA-NICERF-V1") (pin "DIO2") (pinfunction "DIO2_DIO2") (pintype "bidirectional"))
    )
    (net (code "71") (name "unconnected-(LORA-NICERF-V1-PadNC)") (class "Default")
      (node (ref "LORA-NICERF-V1") (pin "NC") (pinfunction "NC_NC") (pintype "bidirectional"))
    )
    (net (code "72") (name "unconnected-(LORA-NICERF-V1-PadNC1)") (class "Default")
      (node (ref "LORA-NICERF-V1") (pin "NC1") (pinfunction "NC1_NC1") (pintype "bidirectional"))
    )
    (net (code "73") (name "unconnected-(MD1-CLK-Pad20)") (class "Default")
      (node (ref "MD1") (pin "20") (pinfunction "CLK_20") (pintype "bidirectional"))
    )
    (net (code "74") (name "unconnected-(MD1-CMD-Pad19)") (class "Default")
      (node (ref "MD1") (pin "19") (pinfunction "CMD_19") (pintype "bidirectional"))
    )
    (net (code "75") (name "unconnected-(MD1-IO2-Pad24)") (class "Default")
      (node (ref "MD1") (pin "24") (pinfunction "IO2_24") (pintype "bidirectional"))
    )
    (net (code "76") (name "unconnected-(MD1-IO12-Pad14)") (class "Default")
      (node (ref "MD1") (pin "14") (pinfunction "IO12_14") (pintype "bidirectional"))
    )
    (net (code "77") (name "unconnected-(MD1-IO13-Pad16)") (class "Default")
      (node (ref "MD1") (pin "16") (pinfunction "IO13_16") (pintype "bidirectional"))
    )
    (net (code "78") (name "unconnected-(MD1-IO34-Pad6)") (class "Default")
      (node (ref "MD1") (pin "6") (pinfunction "IO34_6") (pintype "bidirectional"))
    )
    (net (code "79") (name "unconnected-(MD1-IO35-Pad7)") (class "Default")
      (node (ref "MD1") (pin "7") (pinfunction "IO35_7") (pintype "bidirectional"))
    )
    (net (code "80") (name "unconnected-(MD1-NC-Pad32)") (class "Default")
      (node (ref "MD1") (pin "32") (pinfunction "NC_32") (pintype "passive"))
    )
    (net (code "81") (name "unconnected-(MD1-SD0-Pad21)") (class "Default")
      (node (ref "MD1") (pin "21") (pinfunction "SD0_21") (pintype "bidirectional"))
    )
    (net (code "82") (name "unconnected-(MD1-SD1-Pad22)") (class "Default")
      (node (ref "MD1") (pin "22") (pinfunction "SD1_22") (pintype "bidirectional"))
    )
    (net (code "83") (name "unconnected-(MD1-SD2-Pad17)") (class "Default")
      (node (ref "MD1") (pin "17") (pinfunction "SD2_17") (pintype "bidirectional"))
    )
    (net (code "84") (name "unconnected-(MD1-SD3-Pad18)") (class "Default")
      (node (ref "MD1") (pin "18") (pinfunction "SD3_18") (pintype "bidirectional"))
    )
    (net (code "85") (name "unconnected-(MD1-SENSOR_VN-Pad5)") (class "Default")
      (node (ref "MD1") (pin "5") (pinfunction "SENSOR_VN_5") (pintype "input"))
    )
    (net (code "86") (name "unconnected-(MD1-SENSOR_VP-Pad4)") (class "Default")
      (node (ref "MD1") (pin "4") (pinfunction "SENSOR_VP_4") (pintype "input"))
    )
    (net (code "87") (name "unconnected-(U$2-CTS-Pad9)") (class "Default")
      (node (ref "U$2") (pin "9") (pinfunction "CTS_9") (pintype "bidirectional"))
    )
    (net (code "88") (name "unconnected-(U$2-DCD-Pad12)") (class "Default")
      (node (ref "U$2") (pin "12") (pinfunction "DCD_12") (pintype "bidirectional"))
    )
    (net (code "89") (name "unconnected-(U$2-DSR-Pad10)") (class "Default")
      (node (ref "U$2") (pin "10") (pinfunction "DSR_10") (pintype "bidirectional"))
    )
    (net (code "90") (name "unconnected-(U$2-RI-Pad11)") (class "Default")
      (node (ref "U$2") (pin "11") (pinfunction "RI_11") (pintype "bidirectional"))
    )
    (net (code "91") (name "unconnected-(U$2-RS232-Pad15)") (class "Default")
      (node (ref "U$2") (pin "15") (pinfunction "RS232_15") (pintype "bidirectional"))
    )
    (net (code "92") (name "unconnected-(U1-BP-Pad4)") (class "Default")
      (node (ref "U1") (pin "4") (pinfunction "BP_4") (pintype "passive"))
    )
    (net (code "93") (name "unconnected-(U2-BP-Pad4)") (class "Default")
      (node (ref "U2") (pin "4") (pinfunction "BP_4") (pintype "passive"))
    )
  )
)
